# base.net
KiCad netlist of a schematic drawn in EAGLE
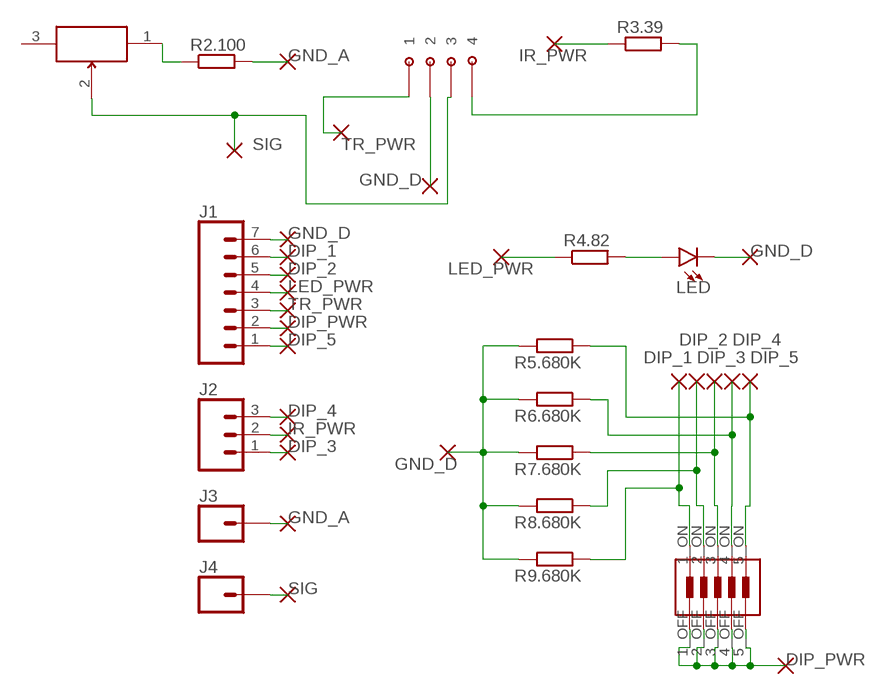
[diagram p0: schematic, sheet 1]

(export (version "E")
  (design (tool "Eeschema 10.0.6"))
  (components
    (comp (ref "J1")
      (value "CONN_07")
      (footprint "eagle-import:1X07")
      (libsource (lib "eagle-import") (part "CONN_07"))
    )
    (comp (ref "J2")
      (value "CONN_03")
      (footprint "eagle-import:1X03")
      (libsource (lib "eagle-import") (part "CONN_03"))
    )
    (comp (ref "J3")
      (value "CONN_01")
      (footprint "eagle-import:1X01")
      (libsource (lib "eagle-import") (part "CONN_01"))
    )
    (comp (ref "J4")
      (value "CONN_01")
      (footprint "eagle-import:1X01")
      (libsource (lib "eagle-import") (part "CONN_01"))
    )
    (comp (ref "LED")
      (value "LED-3MM-NO_SILK")
      (footprint "eagle-import:LED_3MM-NS")
      (libsource (lib "eagle-import") (part "LED-3MM-NO_SILK"))
    )
    (comp (ref "R2.100")
      (value "R-EU_0204/7")
      (footprint "eagle-import:0204_7")
      (libsource (lib "eagle-import") (part "R-EU_0204/7"))
    )
    (comp (ref "R3.39")
      (value "R-EU_0204/7")
      (footprint "eagle-import:0204_7")
      (libsource (lib "eagle-import") (part "R-EU_0204/7"))
    )
    (comp (ref "R4.82")
      (value "R-EU_0204/7")
      (footprint "eagle-import:0204_7")
      (libsource (lib "eagle-import") (part "R-EU_0204/7"))
    )
    (comp (ref "R5.680K")
      (value "R-EU_0204/7")
      (footprint "eagle-import:0204_7")
      (libsource (lib "eagle-import") (part "R-EU_0204/7"))
    )
    (comp (ref "R6.680K")
      (value "R-EU_0204/7")
      (footprint "eagle-import:0204_7")
      (libsource (lib "eagle-import") (part "R-EU_0204/7"))
    )
    (comp (ref "R7.680K")
      (value "R-EU_0204/7")
      (footprint "eagle-import:0204_7")
      (libsource (lib "eagle-import") (part "R-EU_0204/7"))
    )
    (comp (ref "R8.680K")
      (value "R-EU_0204/7")
      (footprint "eagle-import:0204_7")
      (libsource (lib "eagle-import") (part "R-EU_0204/7"))
    )
    (comp (ref "R9.680K")
      (value "R-EU_0204/7")
      (footprint "eagle-import:0204_7")
      (libsource (lib "eagle-import") (part "R-EU_0204/7"))
    )
    (comp (ref "U$1")
      (value "DF1BZ-4DP-2.5DS")
      (footprint "eagle-import:DF1BZ-4DP-2.5DS")
      (libsource (lib "eagle-import") (part "DF1BZ-4DP-2.5DS"))
    )
    (comp (ref "U$2")
      (value "DIP-SW-CTS-208-5")
      (footprint "eagle-import:DIP-SW-CTS-208-5")
      (libsource (lib "eagle-import") (part "DIP-SW-CTS-208-5"))
    )
    (comp (ref "U$3")
      (value "CT6EP103")
      (footprint "eagle-import:CT6EP103")
      (libsource (lib "eagle-import") (part "CT6EP103"))
    )
  )
  (nets
    (net (code "1") (name "/DIP_1") (class "Default")
      (node (ref "J1") (pin "6") (pinfunction "6_6") (pintype "passive"))
      (node (ref "R9.680K") (pin "1") (pinfunction "1_1") (pintype "passive"))
      (node (ref "U$2") (pin "1_ON") (pinfunction "1_ON_1_ON") (pintype "bidirectional"))
    )
    (net (code "2") (name "/DIP_2") (class "Default")
      (node (ref "J1") (pin "5") (pinfunction "5_5") (pintype "passive"))
      (node (ref "R8.680K") (pin "1") (pinfunction "1_1") (pintype "passive"))
      (node (ref "U$2") (pin "2_ON") (pinfunction "2_ON_2_ON") (pintype "bidirectional"))
    )
    (net (code "3") (name "/DIP_3") (class "Default")
      (node (ref "J2") (pin "1") (pinfunction "1_1") (pintype "passive"))
      (node (ref "R7.680K") (pin "1") (pinfunction "1_1") (pintype "passive"))
      (node (ref "U$2") (pin "3_ON") (pinfunction "3_ON_3_ON") (pintype "bidirectional"))
    )
    (net (code "4") (name "/DIP_4") (class "Default")
      (node (ref "J2") (pin "3") (pinfunction "3_3") (pintype "passive"))
      (node (ref "R6.680K") (pin "1") (pinfunction "1_1") (pintype "passive"))
      (node (ref "U$2") (pin "4_ON") (pinfunction "4_ON_4_ON") (pintype "bidirectional"))
    )
    (net (code "5") (name "/DIP_5") (class "Default")
      (node (ref "J1") (pin "1") (pinfunction "1_1") (pintype "passive"))
      (node (ref "R5.680K") (pin "1") (pinfunction "1_1") (pintype "passive"))
      (node (ref "U$2") (pin "5_ON") (pinfunction "5_ON_5_ON") (pintype "bidirectional"))
    )
    (net (code "6") (name "/DIP_PWR") (class "Default")
      (node (ref "J1") (pin "2") (pinfunction "2_2") (pintype "passive"))
      (node (ref "U$2") (pin "1_OFF") (pinfunction "1_OFF_1_OFF") (pintype "bidirectional"))
      (node (ref "U$2") (pin "2_OFF") (pinfunction "2_OFF_2_OFF") (pintype "bidirectional"))
      (node (ref "U$2") (pin "3_OFF") (pinfunction "3_OFF_3_OFF") (pintype "bidirectional"))
      (node (ref "U$2") (pin "4_OFF") (pinfunction "4_OFF_4_OFF") (pintype "bidirectional"))
      (node (ref "U$2") (pin "5_OFF") (pinfunction "5_OFF_5_OFF") (pintype "bidirectional"))
    )
    (net (code "7") (name "/GND_A") (class "Default")
      (node (ref "J3") (pin "1") (pinfunction "1_1") (pintype "passive"))
      (node (ref "R2.100") (pin "2") (pinfunction "2_2") (pintype "passive"))
    )
    (net (code "8") (name "/GND_D") (class "Default")
      (node (ref "J1") (pin "7") (pinfunction "7_7") (pintype "passive"))
      (node (ref "LED") (pin "K") (pinfunction "C_K") (pintype "passive"))
      (node (ref "R5.680K") (pin "2") (pinfunction "2_2") (pintype "passive"))
      (node (ref "R6.680K") (pin "2") (pinfunction "2_2") (pintype "passive"))
      (node (ref "R7.680K") (pin "2") (pinfunction "2_2") (pintype "passive"))
      (node (ref "R8.680K") (pin "2") (pinfunction "2_2") (pintype "passive"))
      (node (ref "R9.680K") (pin "2") (pinfunction "2_2") (pintype "passive"))
      (node (ref "U$1") (pin "2") (pinfunction "2_2") (pintype "power_in"))
    )
    (net (code "9") (name "/IR_PWR") (class "Default")
      (node (ref "J2") (pin "2") (pinfunction "2_2") (pintype "passive"))
      (node (ref "R3.39") (pin "1") (pinfunction "1_1") (pintype "passive"))
    )
    (net (code "10") (name "/LED_PWR") (class "Default")
      (node (ref "J1") (pin "4") (pinfunction "4_4") (pintype "passive"))
      (node (ref "R4.82") (pin "1") (pinfunction "1_1") (pintype "passive"))
    )
    (net (code "11") (name "/P$1") (class "Default")
      (node (ref "U$3") (pin "3") (pinfunction "P$1_3") (pintype "power_in"))
    )
    (net (code "12") (name "/SIG") (class "Default")
      (node (ref "J4") (pin "1") (pinfunction "1_1") (pintype "passive"))
      (node (ref "U$1") (pin "3") (pinfunction "3_3") (pintype "power_in"))
      (node (ref "U$3") (pin "2") (pinfunction "P$2_2") (pintype "power_in"))
    )
    (net (code "13") (name "/TR_PWR") (class "Default")
      (node (ref "J1") (pin "3") (pinfunction "3_3") (pintype "passive"))
      (node (ref "U$1") (pin "1") (pinfunction "1_1") (pintype "power_in"))
    )
    (net (code "14") (name "Net-(LED-PadA)") (class "Default")
      (node (ref "LED") (pin "A") (pinfunction "A_A") (pintype "passive"))
      (node (ref "R4.82") (pin "2") (pinfunction "2_2") (pintype "passive"))
    )
    (net (code "15") (name "Net-(R3.39-Pad2)") (class "Default")
      (node (ref "R3.39") (pin "2") (pinfunction "2_2") (pintype "passive"))
      (node (ref "U$1") (pin "4") (pinfunction "4_4") (pintype "power_in"))
    )
    (net (code "16") (name "Net-(U$3-P$3)") (class "Default")
      (node (ref "R2.100") (pin "1") (pinfunction "1_1") (pintype "passive"))
      (node (ref "U$3") (pin "1") (pinfunction "P$3_1") (pintype "power_in"))
    )
  )
)
